# S1.net
KiCad netlist of a schematic drawn in Altium Designer
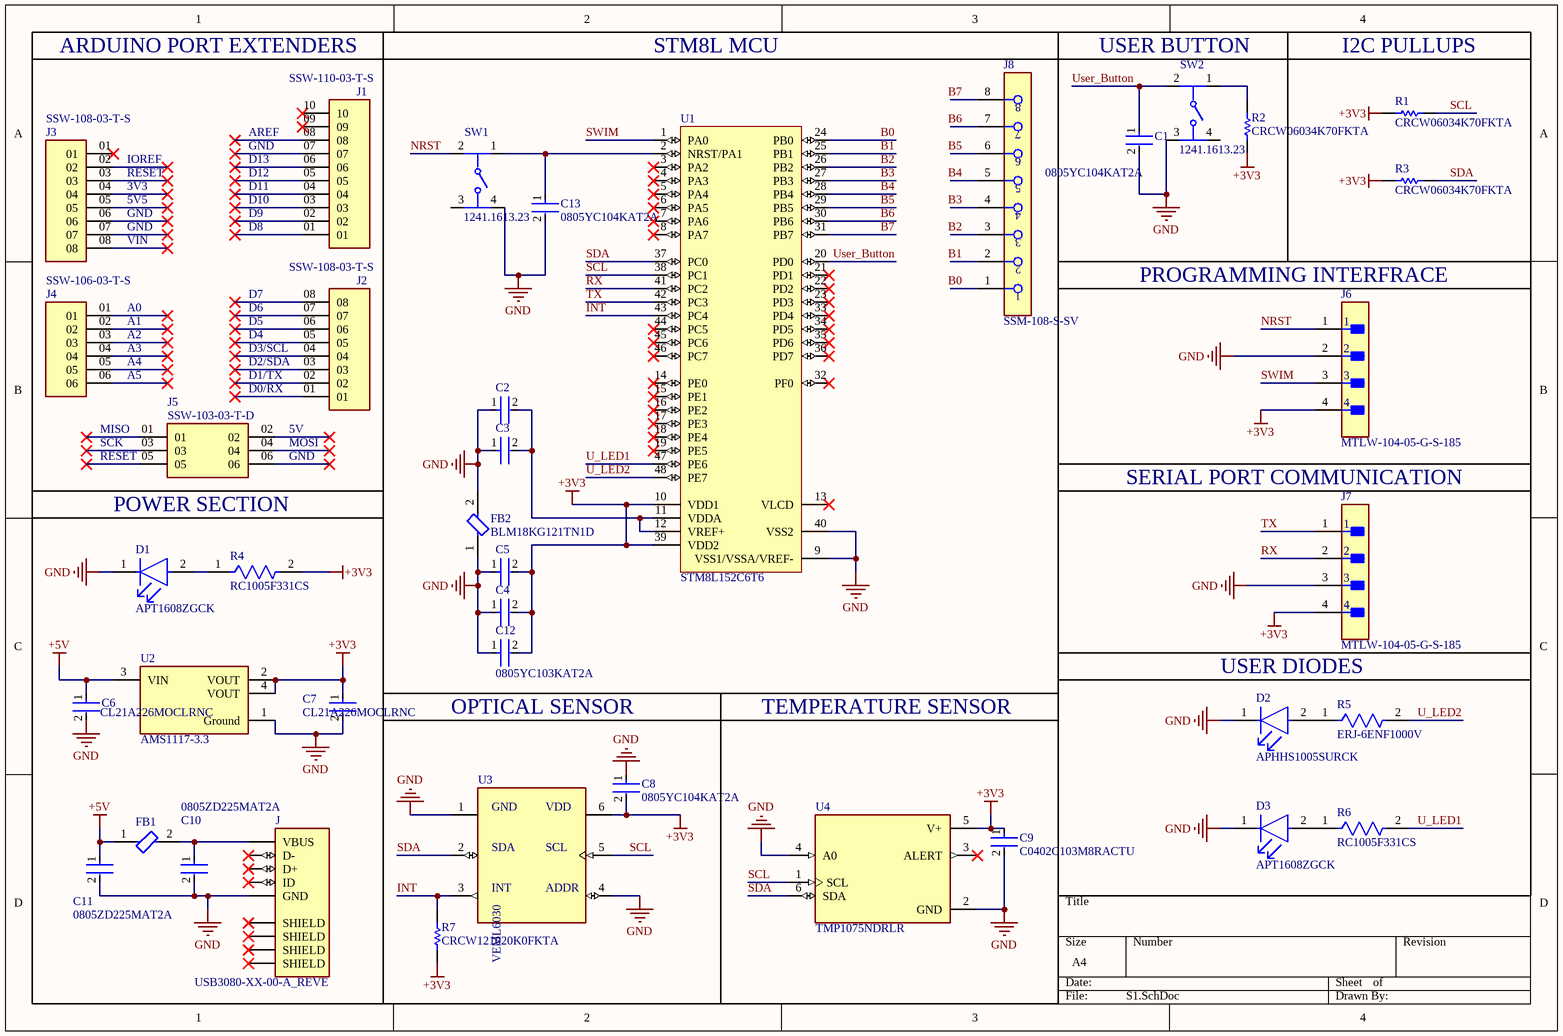
[diagram p0: S1.SchDoc]

(export (version "E")
  (design (tool "Eeschema 10.0.6"))
  (components
    (comp (ref "C1")
      (value "0805YC104KAT2A")
      (footprint "FP-0805-L_2_01_0_2-W_1_25-MFG")
      (description "General Purpose Ceramic Capacitor, 0805, 100nF, 10%, X7R, 0.15, 16V")
      (fields (field (name "TOLERANCE") "10%"))
      (libsource (lib "Altium Content Vault") (part "02cd4be3c70576c341d710602a673aa"))
    )
    (comp (ref "C2")
      (value "0805YC104KAT2A")
      (footprint "FP-0805-L_2_01_0_2-W_1_25-MFG")
      (description "General Purpose Ceramic Capacitor, 0805, 100nF, 10%, X7R, 0.15, 16V")
      (fields (field (name "TOLERANCE") "10%"))
      (libsource (lib "Altium Content Vault") (part "02cd4be3c70576c341d710602a673aa"))
    )
    (comp (ref "C3")
      (value "0805YC104KAT2A")
      (footprint "FP-0805-L_2_01_0_2-W_1_25-MFG")
      (description "General Purpose Ceramic Capacitor, 0805, 100nF, 10%, X7R, 0.15, 16V")
      (fields (field (name "TOLERANCE") "10%"))
      (libsource (lib "Altium Content Vault") (part "02cd4be3c70576c341d710602a673aa"))
    )
    (comp (ref "C4")
      (value "0805YC104KAT2A")
      (footprint "FP-0805-L_2_01_0_2-W_1_25-MFG")
      (description "General Purpose Ceramic Capacitor, 0805, 100nF, 10%, X7R, 0.15, 16V")
      (fields (field (name "TOLERANCE") "10%"))
      (libsource (lib "Altium Content Vault") (part "02cd4be3c70576c341d710602a673aa"))
    )
    (comp (ref "C5")
      (value "0805YC104KAT2A")
      (footprint "FP-0805-L_2_01_0_2-W_1_25-MFG")
      (description "General Purpose Ceramic Capacitor, 0805, 100nF, 10%, X7R, 0.15, 16V")
      (fields (field (name "TOLERANCE") "10%"))
      (libsource (lib "Altium Content Vault") (part "02cd4be3c70576c341d710602a673aa"))
    )
    (comp (ref "C6")
      (value "CL21A226MOCLRNC")
      (footprint "FP-CL21-IPC_C")
      (description "CL21 Series 0805 22uF 16V ±20% Tolerance X5R Multilayer Ceramic Chip Capacitor")
      (fields (field (name "TOLERANCE") "20%"))
      (libsource (lib "Altium Content Vault") (part "b4654b650e69147ec39a6b967a45e02"))
    )
    (comp (ref "C7")
      (value "CL21A226MOCLRNC")
      (footprint "FP-CL21-IPC_C")
      (description "CL21 Series 0805 22uF 16V ±20% Tolerance X5R Multilayer Ceramic Chip Capacitor")
      (fields (field (name "TOLERANCE") "20%"))
      (libsource (lib "Altium Content Vault") (part "b4654b650e69147ec39a6b967a45e02"))
    )
    (comp (ref "C8")
      (value "0805YC104KAT2A")
      (footprint "FP-0805-L_2_01_0_2-W_1_25-MFG")
      (description "General Purpose Ceramic Capacitor, 0805, 100nF, 10%, X7R, 0.15, 16V")
      (fields (field (name "TOLERANCE") "10%"))
      (libsource (lib "Altium Content Vault") (part "02cd4be3c70576c341d710602a673aa"))
    )
    (comp (ref "C9")
      (value "C0402C103M8RACTU")
      (footprint "FP-C0402-BB-MFG")
      (description "CAP CER 10000PF 10V X7R 0402")
      (fields
        (field (name "TOLERANCE") "0.2")
        (field (name "OCTOPART") "https://octopart.com/c0402c103m8ractu-kemet-12595671")
      )
      (libsource (lib "Altium Content Vault") (part "b4654b650e69147ec39a6b967a45e02"))
    )
    (comp (ref "C10")
      (value "0805ZD225MAT2A")
      (footprint "FP-0805-L_2_01_0_2-W_1_25-IPC_B")
      (description "General Purpose Ceramic Capacitor, 0805, 2.2uF, 20%, X5R, 15%, 10V")
      (fields (field (name "TOLERANCE") "20%"))
      (libsource (lib "Altium Content Vault") (part "b4654b650e69147ec39a6b967a45e02"))
    )
    (comp (ref "C11")
      (value "0805ZD225MAT2A")
      (footprint "FP-0805-L_2_01_0_2-W_1_25-IPC_B")
      (description "General Purpose Ceramic Capacitor, 0805, 2.2uF, 20%, X5R, 15%, 10V")
      (fields (field (name "TOLERANCE") "20%"))
      (libsource (lib "Altium Content Vault") (part "b4654b650e69147ec39a6b967a45e02"))
    )
    (comp (ref "C12")
      (value "0805YC103KAT2A")
      (footprint "FP-0805-L_2_01_0_2-W_1_25-IPC_C")
      (description "General Purpose Ceramic Capacitor, 0805, 10nF, 10%, X7R, 0.15, 16V")
      (fields (field (name "TOLERANCE") "10%"))
      (libsource (lib "Altium Content Vault") (part "02cd4be3c70576c341d710602a673aa"))
    )
    (comp (ref "C13")
      (value "0805YC104KAT2A")
      (footprint "FP-0805-L_2_01_0_2-W_1_25-MFG")
      (description "General Purpose Ceramic Capacitor, 0805, 100nF, 10%, X7R, 0.15, 16V")
      (fields (field (name "TOLERANCE") "10%"))
      (libsource (lib "Altium Content Vault") (part "02cd4be3c70576c341d710602a673aa"))
    )
    (comp (ref "D1")
      (value "APT1608ZGCK")
      (footprint "FP-APT1608ZGCK-MFG")
      (description "LED GREEN CLEAR CHIP SMD")
      (libsource (lib "Altium Content Vault") (part "8706943c75ba83719d021d2fdc84c58"))
    )
    (comp (ref "D2")
      (value "APHHS1005SURCK")
      (footprint "FP-APHHS1005SURCK-MFG")
      (description "LED RED CLEAR CHIP SMD")
      (libsource (lib "Altium Content Vault") (part "8706943c75ba83719d021d2fdc84c58"))
    )
    (comp (ref "D3")
      (value "APT1608ZGCK")
      (footprint "FP-APT1608ZGCK-MFG")
      (description "LED GREEN CLEAR CHIP SMD")
      (libsource (lib "Altium Content Vault") (part "8706943c75ba83719d021d2fdc84c58"))
    )
    (comp (ref "FB1")
      (value "BLM18KG121TN1D")
      (footprint "FP-BLM18-0_15-t0_6-d1_2-IPC_A")
      (description "FERRITE BEAD 120 OHM 0603 1LN")
      (fields (field (name "TOLERANCE") "25%"))
      (libsource (lib "Altium Content Vault") (part "5f30dd21d616792df468990f7003faa"))
    )
    (comp (ref "FB2")
      (value "BLM18KG121TN1D")
      (footprint "FP-BLM18-0_15-t0_6-d1_2-IPC_A")
      (description "FERRITE BEAD 120 OHM 0603 1LN")
      (fields (field (name "TOLERANCE") "25%"))
      (libsource (lib "Altium Content Vault") (part "5f30dd21d616792df468990f7003faa"))
    )
    (comp (ref "J")
      (value "USB3080-XX-00-A_REVE")
      (footprint "GCT_USB3080-XX-00-A_REVE")
      (description "USB - micro B USB 2.0 Receptacle Connector 5 Position Surface Mount, Right Angle")
      (fields (field (name "MF") "Global Connector Technology") (field (name "MP") "USB3080-30-00-A"))
      (libsource (lib "USB3080-XX-00-A_REVE") (part "USB3080-XX-00-A_REVE"))
    )
    (comp (ref "J1")
      (value "SSW-110-03-T-S")
      (footprint "SAMTEC_SSW-110-03-T-S")
      (fields (field (name "MF") "Samtec"))
      (libsource (lib "SSW-110-03-T-S") (part "SSW-110-03-T-S"))
    )
    (comp (ref "J2")
      (value "SSW-108-03-T-S")
      (footprint "SAMTEC_SSW-108-XX-X-S")
      (description "8 Position Receptacle Connector Through Hole, Right Angle")
      (fields (field (name "MP") "SSW-108-03-F-S") (field (name "MF") "Samtec"))
      (libsource (lib "SSW-108-03-T-S") (part "SSW-108-XX-X-S"))
    )
    (comp (ref "J3")
      (value "SSW-108-03-T-S")
      (footprint "SAMTEC_SSW-108-XX-X-S")
      (description "8 Position Receptacle Connector Through Hole, Right Angle")
      (fields (field (name "MP") "SSW-108-03-F-S") (field (name "MF") "Samtec"))
      (libsource (lib "") (part "SSW-108-XX-X-S_1"))
    )
    (comp (ref "J4")
      (value "SSW-106-03-T-S")
      (footprint "SAMTEC_SSW-106-03-T-S")
      (fields (field (name "MF") "Samtec Inc."))
      (libsource (lib "SSW-106-03-T-S") (part "SSW-106-03-T-S"))
    )
    (comp (ref "J5")
      (value "SSW-103-03-T-D")
      (footprint "SAMTEC_SSW-103-03-T-D")
      (description "SSW Series .100 Tiger Buyâ„¢ Socket Strip")
      (fields (field (name "MF") "Samtec"))
      (libsource (lib "SSW-103-03-T-D") (part "SSW-103-03-T-D"))
    )
    (comp (ref "J6")
      (value "MTLW-104-05-G-S-185")
      (footprint "FP-MTLW-104-05-G-S-185-MFG")
      (description "CONN HEADER VERT 4POS 2.54MM")
      (libsource (lib "Altium Content Vault") (part "299a8cea1bdcbc3624fe62c390fa72c"))
    )
    (comp (ref "J7")
      (value "MTLW-104-05-G-S-185")
      (footprint "FP-MTLW-104-05-G-S-185-MFG")
      (description "CONN HEADER VERT 4POS 2.54MM")
      (libsource (lib "Altium Content Vault") (part "299a8cea1bdcbc3624fe62c390fa72c"))
    )
    (comp (ref "J8")
      (value "SSM-108-S-SV")
      (footprint "FP-SSM-108-S-SV-MFG")
      (description "CONN RCPT 8POS 0.1 GOLD SMD")
      (libsource (lib "Altium Content Vault") (part "a32a9c29f5c2290c50060dfb8ad7212"))
    )
    (comp (ref "R1")
      (value "CRCW06034K70FKTA")
      (footprint "RESC1609X50X30NL10T20")
      (fields (field (name "MANUFACTURER") "Vishay Dale"))
      (libsource (lib "Altium Content Vault") (part "RES"))
    )
    (comp (ref "R2")
      (value "CRCW06034K70FKTA")
      (footprint "RESC1609X50X30NL10T20")
      (fields (field (name "MANUFACTURER") "Vishay Dale"))
      (libsource (lib "Altium Content Vault") (part "RES"))
    )
    (comp (ref "R3")
      (value "CRCW06034K70FKTA")
      (footprint "RESC1609X50X30NL10T20")
      (fields (field (name "MANUFACTURER") "Vishay Dale"))
      (libsource (lib "Altium Content Vault") (part "RES"))
    )
    (comp (ref "R4")
      (value "RC1005F331CS")
      (footprint "FP-RC1005-IPC_B")
      (description "Res Thick Film 0402 330Ω 1% 0.063W ±100ppm/°C Molded SMD T/R")
      (fields (field (name "TOLERANCE") "1%"))
      (libsource (lib "Altium Content Vault") (part "1029c3af85768c4190bb7ad29bc67b5"))
    )
    (comp (ref "R5")
      (value "ERJ-6ENF1000V")
      (footprint "FP-ERJ6EN-MFG")
      (description "RES SMD 100 OHM 1% 1/8W 0805")
      (fields (field (name "TOLERANCE") "1%"))
      (libsource (lib "Altium Content Vault") (part "1029c3af85768c4190bb7ad29bc67b5"))
    )
    (comp (ref "R6")
      (value "RC1005F331CS")
      (footprint "FP-RC1005-IPC_B")
      (description "Res Thick Film 0402 330Ω 1% 0.063W ±100ppm/°C Molded SMD T/R")
      (fields (field (name "TOLERANCE") "1%"))
      (libsource (lib "Altium Content Vault") (part "1029c3af85768c4190bb7ad29bc67b5"))
    )
    (comp (ref "R7")
      (value "CRCW121020K0FKTA")
      (footprint "RESC3225X60X45LL20T20")
      (fields (field (name "MANUFACTURER") "Vishay Dale"))
      (libsource (lib "Altium Content Vault") (part "RES"))
    )
    (comp (ref "SW1")
      (value "1241.1613.23")
      (footprint "FP-1241_1613_23-MFG")
      (description "SWITCH TACTILE SPST-NO 0.05A 42V")
      (libsource (lib "Altium Content Vault") (part "512b1658425e80dc09bd29e095ee4d3"))
    )
    (comp (ref "SW2")
      (value "1241.1613.23")
      (footprint "FP-1241_1613_23-MFG")
      (description "SWITCH TACTILE SPST-NO 0.05A 42V")
      (libsource (lib "Altium Content Vault") (part "512b1658425e80dc09bd29e095ee4d3"))
    )
    (comp (ref "U1")
      (value "STM8L152C6T6")
      (footprint "LQFP48_M")
      (libsource (lib "Altium Content Vault") (part "MC-ARM-STM8L152-SQ48"))
    )
    (comp (ref "U2")
      (value "AMS1117-3.3")
      (footprint "FP-AMS1117-IPC_C")
      (description "LDO Voltage Regulators 1A, 3.3V")
      (fields
        (field (name "OCTOPART") "https://octopart.com/ams1117-3.3-advanced+monolithic+systems-25899300")
        (field (name "MANUFACTURER") "Advanced Monolithic Systems")
      )
      (libsource (lib "Altium Content Vault") (part "8bdbb5f8e77002000e30dd2845d0354"))
    )
    (comp (ref "U3")
      (value "VEML6030")
      (footprint "VISHAY_VEML6030_2X2X0.87")
      (description "Optical Sensor Ambient 550nm IÂ²C 6-SMD, No Lead")
      (fields (field (name "MF") "Vishay"))
      (libsource (lib "VEML6030") (part "VEML6030"))
    )
    (comp (ref "U4")
      (value "TMP1075NDRLR")
      (footprint "SOT50P160X60-6N")
      (description "1Â°C IÂ²C temperature sensor with performance upgrades to industry standard LM75 / TMP75")
      (fields (field (name "MF") "Texas Instruments"))
      (libsource (lib "TMP1075NDRLR") (part "TMP1075NDRLR"))
    )
  )
  (nets
    (net (code "1") (name "+3V3") (class "Default")
      (node (ref "C12") (pin "2") (pinfunction "2_2") (pintype "passive"))
      (node (ref "C4") (pin "2") (pinfunction "2_2") (pintype "passive"))
      (node (ref "C5") (pin "2") (pinfunction "2_2") (pintype "passive"))
      (node (ref "C7") (pin "1") (pinfunction "1_1") (pintype "passive"))
      (node (ref "C8") (pin "2") (pinfunction "2_2") (pintype "passive"))
      (node (ref "C9") (pin "1") (pinfunction "1_1") (pintype "passive"))
      (node (ref "J6") (pin "4") (pinfunction "4_4") (pintype "passive"))
      (node (ref "J7") (pin "4") (pinfunction "4_4") (pintype "passive"))
      (node (ref "R1") (pin "1") (pinfunction "1_1") (pintype "passive"))
      (node (ref "R2") (pin "1") (pinfunction "1_1") (pintype "passive"))
      (node (ref "R3") (pin "1") (pinfunction "1_1") (pintype "passive"))
      (node (ref "R4") (pin "2") (pinfunction "2_2") (pintype "passive"))
      (node (ref "R7") (pin "1") (pinfunction "1_1") (pintype "passive"))
      (node (ref "U1") (pin "10") (pinfunction "VDD1_10") (pintype "power_in"))
      (node (ref "U1") (pin "39") (pinfunction "VDD2_39") (pintype "power_in"))
      (node (ref "U2") (pin "2") (pinfunction "VOUT_2") (pintype "passive"))
      (node (ref "U2") (pin "4") (pinfunction "VOUT_4") (pintype "passive"))
      (node (ref "U3") (pin "6") (pinfunction "VDD_6") (pintype "power_in"))
      (node (ref "U4") (pin "5") (pinfunction "V+_5") (pintype "power_in"))
    )
    (net (code "2") (name "+5V") (class "Default")
      (node (ref "C11") (pin "1") (pinfunction "1_1") (pintype "passive"))
      (node (ref "C6") (pin "1") (pinfunction "1_1") (pintype "passive"))
      (node (ref "FB1") (pin "1") (pinfunction "1_1") (pintype "passive"))
      (node (ref "U2") (pin "3") (pinfunction "VIN_3") (pintype "power_in"))
    )
    (net (code "3") (name "/B0") (class "Default")
      (node (ref "J8") (pin "1") (pinfunction "1_1") (pintype "passive"))
      (node (ref "U1") (pin "24") (pinfunction "PB0_24") (pintype "bidirectional"))
    )
    (net (code "4") (name "/B1") (class "Default")
      (node (ref "J8") (pin "2") (pinfunction "2_2") (pintype "passive"))
      (node (ref "U1") (pin "25") (pinfunction "PB1_25") (pintype "bidirectional"))
    )
    (net (code "5") (name "/B2") (class "Default")
      (node (ref "J8") (pin "3") (pinfunction "3_3") (pintype "passive"))
      (node (ref "U1") (pin "26") (pinfunction "PB2_26") (pintype "bidirectional"))
    )
    (net (code "6") (name "/B3") (class "Default")
      (node (ref "J8") (pin "4") (pinfunction "4_4") (pintype "passive"))
      (node (ref "U1") (pin "27") (pinfunction "PB3_27") (pintype "bidirectional"))
    )
    (net (code "7") (name "/B4") (class "Default")
      (node (ref "J8") (pin "5") (pinfunction "5_5") (pintype "passive"))
      (node (ref "U1") (pin "28") (pinfunction "PB4_28") (pintype "bidirectional"))
    )
    (net (code "8") (name "/B5") (class "Default")
      (node (ref "J8") (pin "6") (pinfunction "6_6") (pintype "passive"))
      (node (ref "U1") (pin "29") (pinfunction "PB5_29") (pintype "bidirectional"))
    )
    (net (code "9") (name "/B6") (class "Default")
      (node (ref "J8") (pin "7") (pinfunction "7_7") (pintype "passive"))
      (node (ref "U1") (pin "30") (pinfunction "PB6_30") (pintype "bidirectional"))
    )
    (net (code "10") (name "/B7") (class "Default")
      (node (ref "J8") (pin "8") (pinfunction "8_8") (pintype "passive"))
      (node (ref "U1") (pin "31") (pinfunction "PB7_31") (pintype "bidirectional"))
    )
    (net (code "11") (name "/INT") (class "Default")
      (node (ref "R7") (pin "2") (pinfunction "2_2") (pintype "passive"))
      (node (ref "U1") (pin "43") (pinfunction "PC4_43") (pintype "bidirectional"))
      (node (ref "U3") (pin "3") (pinfunction "INT_3") (pintype "output"))
    )
    (net (code "12") (name "/NRST") (class "Default")
      (node (ref "J6") (pin "1") (pinfunction "1_1") (pintype "passive"))
      (node (ref "SW1") (pin "2") (pinfunction "2_2") (pintype "passive"))
    )
    (net (code "13") (name "/RX") (class "Default")
      (node (ref "J7") (pin "2") (pinfunction "2_2") (pintype "passive"))
      (node (ref "U1") (pin "41") (pinfunction "PC2_41") (pintype "bidirectional"))
    )
    (net (code "14") (name "/SCL") (class "Default")
      (node (ref "R1") (pin "2") (pinfunction "2_2") (pintype "passive"))
      (node (ref "U1") (pin "38") (pinfunction "PC1_38") (pintype "bidirectional"))
      (node (ref "U3") (pin "5") (pinfunction "SCL_5") (pintype "input"))
      (node (ref "U4") (pin "1") (pinfunction "SCL_1") (pintype "input"))
    )
    (net (code "15") (name "/SDA") (class "Default")
      (node (ref "R3") (pin "2") (pinfunction "2_2") (pintype "passive"))
      (node (ref "U1") (pin "37") (pinfunction "PC0_37") (pintype "bidirectional"))
      (node (ref "U3") (pin "2") (pinfunction "SDA_2") (pintype "bidirectional"))
      (node (ref "U4") (pin "6") (pinfunction "SDA_6") (pintype "bidirectional"))
    )
    (net (code "16") (name "/SWIM") (class "Default")
      (node (ref "J6") (pin "3") (pinfunction "3_3") (pintype "passive"))
      (node (ref "U1") (pin "1") (pinfunction "PA0_1") (pintype "bidirectional"))
    )
    (net (code "17") (name "/TX") (class "Default")
      (node (ref "J7") (pin "1") (pinfunction "1_1") (pintype "passive"))
      (node (ref "U1") (pin "42") (pinfunction "PC3_42") (pintype "bidirectional"))
    )
    (net (code "18") (name "/U_LED1") (class "Default")
      (node (ref "R6") (pin "2") (pinfunction "2_2") (pintype "passive"))
      (node (ref "U1") (pin "47") (pinfunction "PE6_47") (pintype "bidirectional"))
    )
    (net (code "19") (name "/U_LED2") (class "Default")
      (node (ref "R5") (pin "2") (pinfunction "2_2") (pintype "passive"))
      (node (ref "U1") (pin "48") (pinfunction "PE7_48") (pintype "bidirectional"))
    )
    (net (code "20") (name "/User_Button") (class "Default")
      (node (ref "C1") (pin "1") (pinfunction "1_1") (pintype "passive"))
      (node (ref "SW2") (pin "2") (pinfunction "2_2") (pintype "passive"))
      (node (ref "U1") (pin "20") (pinfunction "PD0_20") (pintype "bidirectional"))
    )
    (net (code "21") (name "GND") (class "Default")
      (node (ref "C1") (pin "2") (pinfunction "2_2") (pintype "passive"))
      (node (ref "C10") (pin "2") (pinfunction "2_2") (pintype "passive"))
      (node (ref "C11") (pin "2") (pinfunction "2_2") (pintype "passive"))
      (node (ref "C12") (pin "1") (pinfunction "1_1") (pintype "passive"))
      (node (ref "C13") (pin "2") (pinfunction "2_2") (pintype "passive"))
      (node (ref "C2") (pin "1") (pinfunction "1_1") (pintype "passive"))
      (node (ref "C3") (pin "1") (pinfunction "1_1") (pintype "passive"))
      (node (ref "C4") (pin "1") (pinfunction "1_1") (pintype "passive"))
      (node (ref "C5") (pin "1") (pinfunction "1_1") (pintype "passive"))
      (node (ref "C6") (pin "2") (pinfunction "2_2") (pintype "passive"))
      (node (ref "C7") (pin "2") (pinfunction "2_2") (pintype "passive"))
      (node (ref "C8") (pin "1") (pinfunction "1_1") (pintype "passive"))
      (node (ref "C9") (pin "2") (pinfunction "2_2") (pintype "passive"))
      (node (ref "D1") (pin "1") (pinfunction "C_1") (pintype "passive"))
      (node (ref "D2") (pin "1") (pinfunction "C_1") (pintype "passive"))
      (node (ref "D3") (pin "1") (pinfunction "C_1") (pintype "passive"))
      (node (ref "FB2") (pin "1") (pinfunction "1_1") (pintype "passive"))
      (node (ref "FB2") (pin "2") (pinfunction "2_2") (pintype "passive"))
      (node (ref "J") (pin "5") (pinfunction "GND_5") (pintype "power_in"))
      (node (ref "J6") (pin "2") (pinfunction "2_2") (pintype "passive"))
      (node (ref "J7") (pin "3") (pinfunction "3_3") (pintype "passive"))
      (node (ref "SW1") (pin "4") (pinfunction "4_4") (pintype "passive"))
      (node (ref "SW2") (pin "3") (pinfunction "3_3") (pintype "passive"))
      (node (ref "U1") (pin "40") (pinfunction "VSS2_40") (pintype "power_in"))
      (node (ref "U1") (pin "9") (pinfunction "VSS1/VSSA/VREF-_9") (pintype "power_in"))
      (node (ref "U2") (pin "1") (pinfunction "Ground_1") (pintype "power_in"))
      (node (ref "U3") (pin "1") (pinfunction "GND_1") (pintype "power_in"))
      (node (ref "U3") (pin "4") (pinfunction "ADDR_4") (pintype "bidirectional"))
      (node (ref "U4") (pin "2") (pinfunction "GND_2") (pintype "power_in"))
      (node (ref "U4") (pin "4") (pinfunction "A0_4") (pintype "input"))
    )
    (net (code "22") (name "Net-(D1-A)") (class "Default")
      (node (ref "D1") (pin "2") (pinfunction "A_2") (pintype "passive"))
      (node (ref "R4") (pin "1") (pinfunction "1_1") (pintype "passive"))
    )
    (net (code "23") (name "Net-(D2-A)") (class "Default")
      (node (ref "D2") (pin "2") (pinfunction "A_2") (pintype "passive"))
      (node (ref "R5") (pin "1") (pinfunction "1_1") (pintype "passive"))
    )
    (net (code "24") (name "Net-(D3-A)") (class "Default")
      (node (ref "D3") (pin "2") (pinfunction "A_2") (pintype "passive"))
      (node (ref "R6") (pin "1") (pinfunction "1_1") (pintype "passive"))
    )
    (net (code "25") (name "Net-(J-VBUS)") (class "Default")
      (node (ref "C10") (pin "1") (pinfunction "1_1") (pintype "passive"))
      (node (ref "FB1") (pin "2") (pinfunction "2_2") (pintype "passive"))
      (node (ref "J") (pin "1") (pinfunction "VBUS_1") (pintype "power_in"))
    )
    (net (code "26") (name "Net-(R2-Pad2)") (class "Default")
      (node (ref "R2") (pin "2") (pinfunction "2_2") (pintype "passive"))
      (node (ref "SW2") (pin "1") (pinfunction "1_1") (pintype "passive"))
    )
    (net (code "27") (name "Net-(U1-NRST{slash}PA1)") (class "Default")
      (node (ref "C13") (pin "1") (pinfunction "1_1") (pintype "passive"))
      (node (ref "SW1") (pin "1") (pinfunction "1_1") (pintype "passive"))
      (node (ref "U1") (pin "2") (pinfunction "NRST/PA1_2") (pintype "bidirectional"))
    )
    (net (code "28") (name "Net-(U1-VDDA)") (class "Default")
      (node (ref "C2") (pin "2") (pinfunction "2_2") (pintype "passive"))
      (node (ref "C3") (pin "2") (pinfunction "2_2") (pintype "passive"))
      (node (ref "U1") (pin "11") (pinfunction "VDDA_11") (pintype "power_in"))
      (node (ref "U1") (pin "12") (pinfunction "VREF+_12") (pintype "power_in"))
    )
    (net (code "29") (name "unconnected-(J-D+-Pad3)") (class "Default")
      (node (ref "J") (pin "3") (pinfunction "D+_3") (pintype "bidirectional+no_connect"))
    )
    (net (code "30") (name "unconnected-(J-D--Pad2)") (class "Default")
      (node (ref "J") (pin "2") (pinfunction "D-_2") (pintype "bidirectional+no_connect"))
    )
    (net (code "31") (name "unconnected-(J-ID-Pad4)") (class "Default")
      (node (ref "J") (pin "4") (pinfunction "ID_4") (pintype "bidirectional+no_connect"))
    )
    (net (code "32") (name "unconnected-(J-SHIELD-Pad6)") (class "Default")
      (node (ref "J") (pin "6") (pinfunction "SHIELD_6") (pintype "power_in+no_connect"))
    )
    (net (code "33") (name "unconnected-(J-SHIELD-Pad7)") (class "Default")
      (node (ref "J") (pin "7") (pinfunction "SHIELD_7") (pintype "power_in+no_connect"))
    )
    (net (code "34") (name "unconnected-(J-SHIELD-Pad8)") (class "Default")
      (node (ref "J") (pin "8") (pinfunction "SHIELD_8") (pintype "power_in+no_connect"))
    )
    (net (code "35") (name "unconnected-(J-SHIELD-Pad9)") (class "Default")
      (node (ref "J") (pin "9") (pinfunction "SHIELD_9") (pintype "power_in+no_connect"))
    )
    (net (code "36") (name "unconnected-(J1-Pad01)") (class "Default")
      (node (ref "J1") (pin "01") (pinfunction "01_01") (pintype "passive+no_connect"))
    )
    (net (code "37") (name "unconnected-(J1-Pad02)") (class "Default")
      (node (ref "J1") (pin "02") (pinfunction "02_02") (pintype "passive+no_connect"))
    )
    (net (code "38") (name "unconnected-(J1-Pad03)") (class "Default")
      (node (ref "J1") (pin "03") (pinfunction "03_03") (pintype "passive+no_connect"))
    )
    (net (code "39") (name "unconnected-(J1-Pad04)") (class "Default")
      (node (ref "J1") (pin "04") (pinfunction "04_04") (pintype "passive+no_connect"))
    )
    (net (code "40") (name "unconnected-(J1-Pad05)") (class "Default")
      (node (ref "J1") (pin "05") (pinfunction "05_05") (pintype "passive+no_connect"))
    )
    (net (code "41") (name "unconnected-(J1-Pad06)") (class "Default")
      (node (ref "J1") (pin "06") (pinfunction "06_06") (pintype "passive+no_connect"))
    )
    (net (code "42") (name "unconnected-(J1-Pad07)") (class "Default")
      (node (ref "J1") (pin "07") (pinfunction "07_07") (pintype "passive+no_connect"))
    )
    (net (code "43") (name "unconnected-(J1-Pad08)") (class "Default")
      (node (ref "J1") (pin "08") (pinfunction "08_08") (pintype "passive+no_connect"))
    )
    (net (code "44") (name "unconnected-(J1-Pad09)") (class "Default")
      (node (ref "J1") (pin "09") (pinfunction "09_09") (pintype "passive+no_connect"))
    )
    (net (code "45") (name "unconnected-(J1-Pad10)") (class "Default")
      (node (ref "J1") (pin "10") (pinfunction "10_10") (pintype "passive+no_connect"))
    )
    (net (code "46") (name "unconnected-(J2-Pad01)") (class "Default")
      (node (ref "J2") (pin "01") (pinfunction "01_01") (pintype "passive+no_connect"))
    )
    (net (code "47") (name "unconnected-(J2-Pad02)") (class "Default")
      (node (ref "J2") (pin "02") (pinfunction "02_02") (pintype "passive+no_connect"))
    )
    (net (code "48") (name "unconnected-(J2-Pad03)") (class "Default")
      (node (ref "J2") (pin "03") (pinfunction "03_03") (pintype "passive+no_connect"))
    )
    (net (code "49") (name "unconnected-(J2-Pad04)") (class "Default")
      (node (ref "J2") (pin "04") (pinfunction "04_04") (pintype "passive+no_connect"))
    )
    (net (code "50") (name "unconnected-(J2-Pad05)") (class "Default")
      (node (ref "J2") (pin "05") (pinfunction "05_05") (pintype "passive+no_connect"))
    )
    (net (code "51") (name "unconnected-(J2-Pad06)") (class "Default")
      (node (ref "J2") (pin "06") (pinfunction "06_06") (pintype "passive+no_connect"))
    )
    (net (code "52") (name "unconnected-(J2-Pad07)") (class "Default")
      (node (ref "J2") (pin "07") (pinfunction "07_07") (pintype "passive+no_connect"))
    )
    (net (code "53") (name "unconnected-(J2-Pad08)") (class "Default")
      (node (ref "J2") (pin "08") (pinfunction "08_08") (pintype "passive+no_connect"))
    )
    (net (code "54") (name "unconnected-(J3-Pad01)") (class "Default")
      (node (ref "J3") (pin "01") (pinfunction "01_01") (pintype "passive+no_connect"))
    )
    (net (code "55") (name "unconnected-(J3-Pad02)") (class "Default")
      (node (ref "J3") (pin "02") (pinfunction "02_02") (pintype "passive+no_connect"))
    )
    (net (code "56") (name "unconnected-(J3-Pad03)") (class "Default")
      (node (ref "J3") (pin "03") (pinfunction "03_03") (pintype "passive+no_connect"))
    )
    (net (code "57") (name "unconnected-(J3-Pad04)") (class "Default")
      (node (ref "J3") (pin "04") (pinfunction "04_04") (pintype "passive+no_connect"))
    )
    (net (code "58") (name "unconnected-(J3-Pad05)") (class "Default")
      (node (ref "J3") (pin "05") (pinfunction "05_05") (pintype "passive+no_connect"))
    )
    (net (code "59") (name "unconnected-(J3-Pad06)") (class "Default")
      (node (ref "J3") (pin "06") (pinfunction "06_06") (pintype "passive+no_connect"))
    )
    (net (code "60") (name "unconnected-(J3-Pad07)") (class "Default")
      (node (ref "J3") (pin "07") (pinfunction "07_07") (pintype "passive+no_connect"))
    )
    (net (code "61") (name "unconnected-(J3-Pad08)") (class "Default")
      (node (ref "J3") (pin "08") (pinfunction "08_08") (pintype "passive+no_connect"))
    )
    (net (code "62") (name "unconnected-(J4-Pad01)") (class "Default")
      (node (ref "J4") (pin "01") (pinfunction "01_01") (pintype "passive+no_connect"))
    )
    (net (code "63") (name "unconnected-(J4-Pad02)") (class "Default")
      (node (ref "J4") (pin "02") (pinfunction "02_02") (pintype "passive+no_connect"))
    )
    (net (code "64") (name "unconnected-(J4-Pad03)") (class "Default")
      (node (ref "J4") (pin "03") (pinfunction "03_03") (pintype "passive+no_connect"))
    )
    (net (code "65") (name "unconnected-(J4-Pad04)") (class "Default")
      (node (ref "J4") (pin "04") (pinfunction "04_04") (pintype "passive+no_connect"))
    )
    (net (code "66") (name "unconnected-(J4-Pad05)") (class "Default")
      (node (ref "J4") (pin "05") (pinfunction "05_05") (pintype "passive+no_connect"))
    )
    (net (code "67") (name "unconnected-(J4-Pad06)") (class "Default")
      (node (ref "J4") (pin "06") (pinfunction "06_06") (pintype "passive+no_connect"))
    )
    (net (code "68") (name "unconnected-(J5-Pad01)") (class "Default")
      (node (ref "J5") (pin "01") (pinfunction "01_01") (pintype "passive+no_connect"))
    )
    (net (code "69") (name "unconnected-(J5-Pad02)") (class "Default")
      (node (ref "J5") (pin "02") (pinfunction "02_02") (pintype "passive+no_connect"))
    )
    (net (code "70") (name "unconnected-(J5-Pad03)") (class "Default")
      (node (ref "J5") (pin "03") (pinfunction "03_03") (pintype "passive+no_connect"))
    )
    (net (code "71") (name "unconnected-(J5-Pad04)") (class "Default")
      (node (ref "J5") (pin "04") (pinfunction "04_04") (pintype "passive+no_connect"))
    )
    (net (code "72") (name "unconnected-(J5-Pad05)") (class "Default")
      (node (ref "J5") (pin "05") (pinfunction "05_05") (pintype "passive+no_connect"))
    )
    (net (code "73") (name "unconnected-(J5-Pad06)") (class "Default")
      (node (ref "J5") (pin "06") (pinfunction "06_06") (pintype "passive+no_connect"))
    )
    (net (code "74") (name "unconnected-(SW1-Pad3)") (class "Default")
      (node (ref "SW1") (pin "3") (pinfunction "3_3") (pintype "passive"))
    )
    (net (code "75") (name "unconnected-(SW2-Pad4)") (class "Default")
      (node (ref "SW2") (pin "4") (pinfunction "4_4") (pintype "passive"))
    )
    (net (code "76") (name "unconnected-(U1-PA2-Pad3)") (class "Default")
      (node (ref "U1") (pin "3") (pinfunction "PA2_3") (pintype "bidirectional+no_connect"))
    )
    (net (code "77") (name "unconnected-(U1-PA3-Pad4)") (class "Default")
      (node (ref "U1") (pin "4") (pinfunction "PA3_4") (pintype "bidirectional+no_connect"))
    )
    (net (code "78") (name "unconnected-(U1-PA4-Pad5)") (class "Default")
      (node (ref "U1") (pin "5") (pinfunction "PA4_5") (pintype "bidirectional+no_connect"))
    )
    (net (code "79") (name "unconnected-(U1-PA5-Pad6)") (class "Default")
      (node (ref "U1") (pin "6") (pinfunction "PA5_6") (pintype "bidirectional+no_connect"))
    )
    (net (code "80") (name "unconnected-(U1-PA6-Pad7)") (class "Default")
      (node (ref "U1") (pin "7") (pinfunction "PA6_7") (pintype "bidirectional+no_connect"))
    )
    (net (code "81") (name "unconnected-(U1-PA7-Pad8)") (class "Default")
      (node (ref "U1") (pin "8") (pinfunction "PA7_8") (pintype "bidirectional+no_connect"))
    )
    (net (code "82") (name "unconnected-(U1-PC5-Pad44)") (class "Default")
      (node (ref "U1") (pin "44") (pinfunction "PC5_44") (pintype "bidirectional+no_connect"))
    )
    (net (code "83") (name "unconnected-(U1-PC6-Pad45)") (class "Default")
      (node (ref "U1") (pin "45") (pinfunction "PC6_45") (pintype "bidirectional+no_connect"))
    )
    (net (code "84") (name "unconnected-(U1-PC7-Pad46)") (class "Default")
      (node (ref "U1") (pin "46") (pinfunction "PC7_46") (pintype "bidirectional+no_connect"))
    )
    (net (code "85") (name "unconnected-(U1-PD1-Pad21)") (class "Default")
      (node (ref "U1") (pin "21") (pinfunction "PD1_21") (pintype "bidirectional+no_connect"))
    )
    (net (code "86") (name "unconnected-(U1-PD2-Pad22)") (class "Default")
      (node (ref "U1") (pin "22") (pinfunction "PD2_22") (pintype "bidirectional+no_connect"))
    )
    (net (code "87") (name "unconnected-(U1-PD3-Pad23)") (class "Default")
      (node (ref "U1") (pin "23") (pinfunction "PD3_23") (pintype "bidirectional+no_connect"))
    )
    (net (code "88") (name "unconnected-(U1-PD4-Pad33)") (class "Default")
      (node (ref "U1") (pin "33") (pinfunction "PD4_33") (pintype "bidirectional+no_connect"))
    )
    (net (code "89") (name "unconnected-(U1-PD5-Pad34)") (class "Default")
      (node (ref "U1") (pin "34") (pinfunction "PD5_34") (pintype "bidirectional+no_connect"))
    )
    (net (code "90") (name "unconnected-(U1-PD6-Pad35)") (class "Default")
      (node (ref "U1") (pin "35") (pinfunction "PD6_35") (pintype "bidirectional+no_connect"))
    )
    (net (code "91") (name "unconnected-(U1-PD7-Pad36)") (class "Default")
      (node (ref "U1") (pin "36") (pinfunction "PD7_36") (pintype "bidirectional+no_connect"))
    )
    (net (code "92") (name "unconnected-(U1-PE0-Pad14)") (class "Default")
      (node (ref "U1") (pin "14") (pinfunction "PE0_14") (pintype "bidirectional+no_connect"))
    )
    (net (code "93") (name "unconnected-(U1-PE1-Pad15)") (class "Default")
      (node (ref "U1") (pin "15") (pinfunction "PE1_15") (pintype "bidirectional+no_connect"))
    )
    (net (code "94") (name "unconnected-(U1-PE2-Pad16)") (class "Default")
      (node (ref "U1") (pin "16") (pinfunction "PE2_16") (pintype "bidirectional+no_connect"))
    )
    (net (code "95") (name "unconnected-(U1-PE3-Pad17)") (class "Default")
      (node (ref "U1") (pin "17") (pinfunction "PE3_17") (pintype "bidirectional+no_connect"))
    )
    (net (code "96") (name "unconnected-(U1-PE4-Pad18)") (class "Default")
      (node (ref "U1") (pin "18") (pinfunction "PE4_18") (pintype "bidirectional+no_connect"))
    )
    (net (code "97") (name "unconnected-(U1-PE5-Pad19)") (class "Default")
      (node (ref "U1") (pin "19") (pinfunction "PE5_19") (pintype "bidirectional+no_connect"))
    )
    (net (code "98") (name "unconnected-(U1-PF0-Pad32)") (class "Default")
      (node (ref "U1") (pin "32") (pinfunction "PF0_32") (pintype "bidirectional+no_connect"))
    )
    (net (code "99") (name "unconnected-(U1-VLCD-Pad13)") (class "Default")
      (node (ref "U1") (pin "13") (pinfunction "VLCD_13") (pintype "passive+no_connect"))
    )
    (net (code "100") (name "unconnected-(U4-ALERT-Pad3)") (class "Default")
      (node (ref "U4") (pin "3") (pinfunction "ALERT_3") (pintype "output+no_connect"))
    )
  )
)
